# karmanDB_gps_gs.net
KiCad netlist of a schematic drawn in Altium Designer
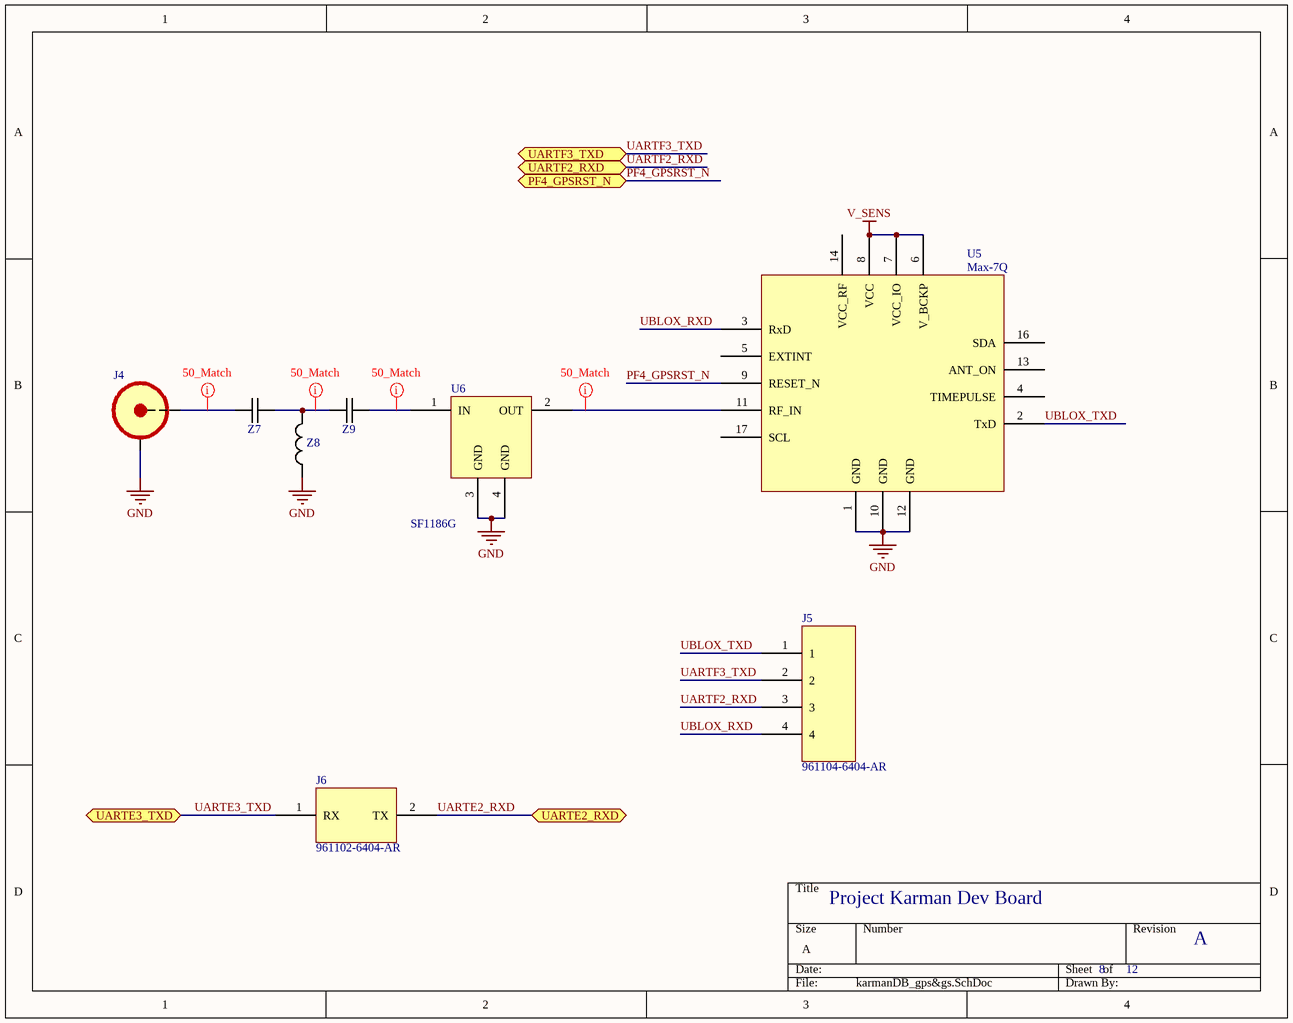
[diagram p0: karmanDB_gps&gs.SchDoc]

(export (version "E")
  (design (tool "Eeschema 10.0.6"))
  (components
    (comp (ref "J4")
      (value "MOLEX_0733910060")
      (footprint "MOLEX_0733910060")
      (description "CONN SMA JACK STR 50 OHM PCB")
      (fields
        (field (name "MANUFACTURER") "Molex Inc")
        (field (name "MANUFACTURER PART NUMBER") "0733910060")
      )
      (libsource (lib "project_symbols") (part "MOLEX_0733910060"))
    )
    (comp (ref "J5")
      (value "961104-6404-AR")
      (footprint "961104-6404-AR")
      (description "CONN HEADER VERT SGL 4POS GOLD")
      (fields (field (name "MANUFACTURER") "3M"))
      (libsource (lib "karman_pcb") (part "961104-6404-AR"))
    )
    (comp (ref "J6")
      (value "961102-6404-AR")
      (footprint "3M_961102-6X04")
      (description "CONN HEADER VERT SGL 2POS GOLD")
      (fields (field (name "MANUFACTURER") "3M"))
      (libsource (lib "karman_pcb") (part "961102-6404-AR"))
    )
    (comp (ref "U5")
      (value "Max-7Q")
      (footprint "11 MAX-7Q")
      (description "MAX-7Q ublox GPS chip")
      (libsource (lib "karman_pcb") (part "Max-7Q"))
    )
    (comp (ref "U6")
      (value "SF1186G")
      (footprint "sf1186g")
      (description "SAW Filter MuRata")
      (libsource (lib "karman_pcb") (part "SF1186G"))
    )
    (comp (ref "Z7")
      (value "CAP_GENERIC_0402")
      (footprint "MURATA_GRM_0402")
      (description "Generic Capacitor 0402 Package")
      (libsource (lib "project_symbols") (part "CAP_GENERIC_0402"))
    )
    (comp (ref "Z8")
      (value "IND_GENERIC_0402")
      (footprint "PANASONIC_ELJRF")
      (description "Generic Inductor 0402 Package")
      (libsource (lib "project_symbols") (part "IND_GENERIC_0402"))
    )
    (comp (ref "Z9")
      (value "CAP_GENERIC_0402")
      (footprint "MURATA_GRM_0402")
      (description "Generic Capacitor 0402 Package")
      (libsource (lib "project_symbols") (part "CAP_GENERIC_0402"))
    )
  )
  (nets
    (net (code "1") (name "/PF4_GPSRST_N") (class "Default")
      (node (ref "U5") (pin "9") (pinfunction "RESET_N_9") (pintype "passive"))
    )
    (net (code "2") (name "/UARTE2_RXD") (class "Default")
      (node (ref "J6") (pin "2") (pinfunction "TX_2") (pintype "passive"))
    )
    (net (code "3") (name "/UARTE3_TXD") (class "Default")
      (node (ref "J6") (pin "1") (pinfunction "RX_1") (pintype "passive"))
    )
    (net (code "4") (name "/UARTF2_RXD") (class "Default")
      (node (ref "J5") (pin "3") (pinfunction "3_3") (pintype "passive"))
    )
    (net (code "5") (name "/UARTF3_TXD") (class "Default")
      (node (ref "J5") (pin "2") (pinfunction "2_2") (pintype "passive"))
    )
    (net (code "6") (name "/UBLOX_RXD") (class "Default")
      (node (ref "J5") (pin "4") (pinfunction "4_4") (pintype "passive"))
      (node (ref "U5") (pin "3") (pinfunction "RxD_3") (pintype "passive"))
    )
    (net (code "7") (name "/UBLOX_TXD") (class "Default")
      (node (ref "J5") (pin "1") (pinfunction "1_1") (pintype "passive"))
      (node (ref "U5") (pin "2") (pinfunction "TxD_2") (pintype "passive"))
    )
    (net (code "8") (name "GND") (class "Default")
      (node (ref "J4") (pin "SHIELD") (pintype "passive"))
      (node (ref "U5") (pin "1") (pinfunction "GND_1") (pintype "passive"))
      (node (ref "U5") (pin "10") (pinfunction "GND_10") (pintype "passive"))
      (node (ref "U5") (pin "12") (pinfunction "GND_12") (pintype "passive"))
      (node (ref "U6") (pin "3") (pinfunction "GND_3") (pintype "passive"))
      (node (ref "U6") (pin "4") (pinfunction "GND_4") (pintype "passive"))
      (node (ref "Z8") (pin "1") (pinfunction "1_1") (pintype "passive"))
    )
    (net (code "9") (name "Net-(J4-PadPIN)") (class "Default")
      (node (ref "J4") (pin "PIN") (pintype "passive"))
      (node (ref "Z7") (pin "1") (pintype "passive"))
    )
    (net (code "10") (name "Net-(U5-RF_IN)") (class "Default")
      (node (ref "U5") (pin "11") (pinfunction "RF_IN_11") (pintype "passive"))
      (node (ref "U6") (pin "2") (pinfunction "OUT_2") (pintype "passive"))
    )
    (net (code "11") (name "Net-(U6-IN)") (class "Default")
      (node (ref "U6") (pin "1") (pinfunction "IN_1") (pintype "passive"))
      (node (ref "Z9") (pin "2") (pintype "passive"))
    )
    (net (code "12") (name "Net-(Z7-Pad2)") (class "Default")
      (node (ref "Z7") (pin "2") (pintype "passive"))
      (node (ref "Z8") (pin "2") (pinfunction "2_2") (pintype "passive"))
      (node (ref "Z9") (pin "1") (pintype "passive"))
    )
    (net (code "13") (name "V_SENS") (class "Default")
      (node (ref "U5") (pin "6") (pinfunction "V_BCKP_6") (pintype "passive"))
      (node (ref "U5") (pin "7") (pinfunction "VCC_IO_7") (pintype "passive"))
      (node (ref "U5") (pin "8") (pinfunction "VCC_8") (pintype "passive"))
    )
    (net (code "14") (name "unconnected-(U5-ANT_ON-Pad13)") (class "Default")
      (node (ref "U5") (pin "13") (pinfunction "ANT_ON_13") (pintype "passive"))
    )
    (net (code "15") (name "unconnected-(U5-EXTINT-Pad5)") (class "Default")
      (node (ref "U5") (pin "5") (pinfunction "EXTINT_5") (pintype "passive"))
    )
    (net (code "16") (name "unconnected-(U5-SCL-Pad17)") (class "Default")
      (node (ref "U5") (pin "17") (pinfunction "SCL_17") (pintype "passive"))
    )
    (net (code "17") (name "unconnected-(U5-SDA-Pad16)") (class "Default")
      (node (ref "U5") (pin "16") (pinfunction "SDA_16") (pintype "passive"))
    )
    (net (code "18") (name "unconnected-(U5-TIMEPULSE-Pad4)") (class "Default")
      (node (ref "U5") (pin "4") (pinfunction "TIMEPULSE_4") (pintype "passive"))
    )
    (net (code "19") (name "unconnected-(U5-VCC_RF-Pad14)") (class "Default")
      (node (ref "U5") (pin "14") (pinfunction "VCC_RF_14") (pintype "passive"))
    )
  )
)
